# H19R1_Frontend_2.net
KiCad netlist of a schematic drawn in Altium Designer
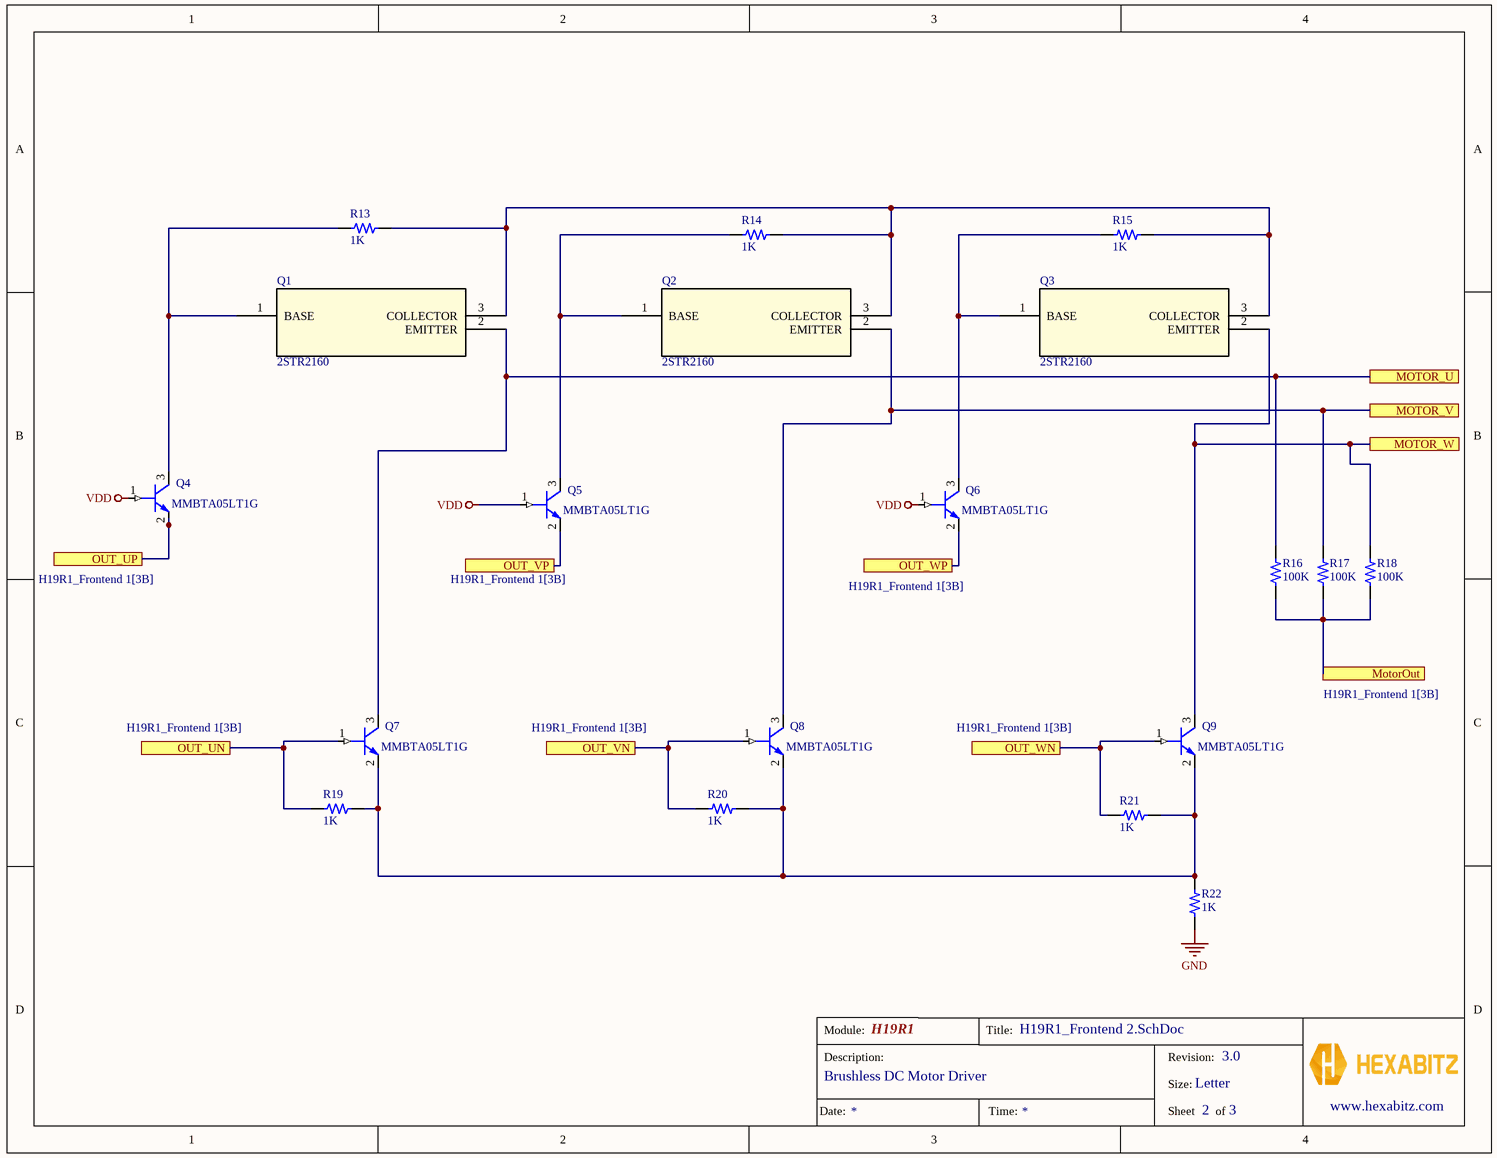
[diagram p0: H19R1_Frontend 2.SchDoc]

(export (version "E")
  (design (tool "Eeschema 10.0.6"))
  (components
    (comp (ref "Q1")
      (value "2STR2160")
      (footprint "SOT23_3P04X1P75X1P9_STM")
      (description "Low voltage fast-switching PNP power transistor")
      (fields (field (name "COPYRIGHT") "Copyright (C) 2025 Ultra Librarian. All rights reserved."))
      (libsource (lib "2STR2160") (part "2STR2160"))
    )
    (comp (ref "Q2")
      (value "2STR2160")
      (footprint "SOT23_3P04X1P75X1P9_STM")
      (description "Low voltage fast-switching PNP power transistor")
      (fields (field (name "COPYRIGHT") "Copyright (C) 2025 Ultra Librarian. All rights reserved."))
      (libsource (lib "2STR2160") (part "2STR2160"))
    )
    (comp (ref "Q3")
      (value "2STR2160")
      (footprint "SOT23_3P04X1P75X1P9_STM")
      (description "Low voltage fast-switching PNP power transistor")
      (fields (field (name "COPYRIGHT") "Copyright (C) 2025 Ultra Librarian. All rights reserved."))
      (libsource (lib "2STR2160") (part "2STR2160"))
    )
    (comp (ref "Q4")
      (value "MMBTA05LT1G")
      (footprint "SOT-23")
      (description "ON Semi MMBTA05LT1G NPN Bipolar Transistor; 0.5 A; 60 V; 3-Pin SOT-23")
      (fields
        (field (name "MANUFACTURER") "ON Semiconductor")
        (field (name "MANUFACTURER PART NUMBER") "MMBTA05LT1G")
      )
      (libsource (lib "Semiconductor") (part "MMBTA05LT1G"))
    )
    (comp (ref "Q5")
      (value "MMBTA05LT1G")
      (footprint "SOT-23")
      (description "ON Semi MMBTA05LT1G NPN Bipolar Transistor; 0.5 A; 60 V; 3-Pin SOT-23")
      (fields
        (field (name "MANUFACTURER") "ON Semiconductor")
        (field (name "MANUFACTURER PART NUMBER") "MMBTA05LT1G")
      )
      (libsource (lib "Semiconductor") (part "MMBTA05LT1G"))
    )
    (comp (ref "Q6")
      (value "MMBTA05LT1G")
      (footprint "SOT-23")
      (description "ON Semi MMBTA05LT1G NPN Bipolar Transistor; 0.5 A; 60 V; 3-Pin SOT-23")
      (fields
        (field (name "MANUFACTURER") "ON Semiconductor")
        (field (name "MANUFACTURER PART NUMBER") "MMBTA05LT1G")
      )
      (libsource (lib "Semiconductor") (part "MMBTA05LT1G"))
    )
    (comp (ref "Q7")
      (value "MMBTA05LT1G")
      (footprint "SOT-23")
      (description "ON Semi MMBTA05LT1G NPN Bipolar Transistor; 0.5 A; 60 V; 3-Pin SOT-23")
      (fields
        (field (name "MANUFACTURER") "ON Semiconductor")
        (field (name "MANUFACTURER PART NUMBER") "MMBTA05LT1G")
      )
      (libsource (lib "Semiconductor") (part "MMBTA05LT1G"))
    )
    (comp (ref "Q8")
      (value "MMBTA05LT1G")
      (footprint "SOT-23")
      (description "ON Semi MMBTA05LT1G NPN Bipolar Transistor; 0.5 A; 60 V; 3-Pin SOT-23")
      (fields
        (field (name "MANUFACTURER") "ON Semiconductor")
        (field (name "MANUFACTURER PART NUMBER") "MMBTA05LT1G")
      )
      (libsource (lib "Semiconductor") (part "MMBTA05LT1G"))
    )
    (comp (ref "Q9")
      (value "MMBTA05LT1G")
      (footprint "SOT-23")
      (description "ON Semi MMBTA05LT1G NPN Bipolar Transistor; 0.5 A; 60 V; 3-Pin SOT-23")
      (fields
        (field (name "MANUFACTURER") "ON Semiconductor")
        (field (name "MANUFACTURER PART NUMBER") "MMBTA05LT1G")
      )
      (libsource (lib "Semiconductor") (part "MMBTA05LT1G"))
    )
    (comp (ref "R13")
      (value "1K")
      (footprint "R0402_3")
      (description "SMD Chip Resistor 1 Kohm ½ 1% 62.5 Mw 0402 [1005 Metric] Thick Film General Purpose")
      (fields
        (field (name "MANUFACTURER") "Yageo")
        (field (name "MANUFACTURER PART NUMBER") "RC0402FR-071KL")
      )
      (libsource (lib "Passive") (part "RC0402FR-071KL"))
    )
    (comp (ref "R14")
      (value "1K")
      (footprint "R0402_3")
      (description "SMD Chip Resistor 1 Kohm ½ 1% 62.5 Mw 0402 [1005 Metric] Thick Film General Purpose")
      (fields
        (field (name "MANUFACTURER") "Yageo")
        (field (name "MANUFACTURER PART NUMBER") "RC0402FR-071KL")
      )
      (libsource (lib "Passive") (part "RC0402FR-071KL"))
    )
    (comp (ref "R15")
      (value "1K")
      (footprint "R0402_3")
      (description "SMD Chip Resistor 1 Kohm ½ 1% 62.5 Mw 0402 [1005 Metric] Thick Film General Purpose")
      (fields
        (field (name "MANUFACTURER") "Yageo")
        (field (name "MANUFACTURER PART NUMBER") "RC0402FR-071KL")
      )
      (libsource (lib "Passive") (part "RC0402FR-071KL"))
    )
    (comp (ref "R16")
      (value "100K")
      (footprint "R0402_3")
      (description "Res Thick Film 0402 100K Ohm 1% 1/10W ±100ppm/°C Molded SMD Punched Carrier T/R")
      (fields
        (field (name "MANUFACTURER") "Panasonic")
        (field (name "MANUFACTURER PART NUMBER") "ERJ-2RKF1003X")
      )
      (libsource (lib "Passive") (part "ERJ-2RKF1003X"))
    )
    (comp (ref "R17")
      (value "100K")
      (footprint "R0402_3")
      (description "Res Thick Film 0402 100K Ohm 1% 1/10W ±100ppm/°C Molded SMD Punched Carrier T/R")
      (fields
        (field (name "MANUFACTURER") "Panasonic")
        (field (name "MANUFACTURER PART NUMBER") "ERJ-2RKF1003X")
      )
      (libsource (lib "Passive") (part "ERJ-2RKF1003X"))
    )
    (comp (ref "R18")
      (value "100K")
      (footprint "R0402_3")
      (description "Res Thick Film 0402 100K Ohm 1% 1/10W ±100ppm/°C Molded SMD Punched Carrier T/R")
      (fields
        (field (name "MANUFACTURER") "Panasonic")
        (field (name "MANUFACTURER PART NUMBER") "ERJ-2RKF1003X")
      )
      (libsource (lib "Passive") (part "ERJ-2RKF1003X"))
    )
    (comp (ref "R19")
      (value "1K")
      (footprint "R0402_3")
      (description "SMD Chip Resistor 1 Kohm ½ 1% 62.5 Mw 0402 [1005 Metric] Thick Film General Purpose")
      (fields
        (field (name "MANUFACTURER") "Yageo")
        (field (name "MANUFACTURER PART NUMBER") "RC0402FR-071KL")
      )
      (libsource (lib "Passive") (part "RC0402FR-071KL"))
    )
    (comp (ref "R20")
      (value "1K")
      (footprint "R0402_3")
      (description "SMD Chip Resistor 1 Kohm ½ 1% 62.5 Mw 0402 [1005 Metric] Thick Film General Purpose")
      (fields
        (field (name "MANUFACTURER") "Yageo")
        (field (name "MANUFACTURER PART NUMBER") "RC0402FR-071KL")
      )
      (libsource (lib "Passive") (part "RC0402FR-071KL"))
    )
    (comp (ref "R21")
      (value "1K")
      (footprint "R0402_3")
      (description "SMD Chip Resistor 1 Kohm ½ 1% 62.5 Mw 0402 [1005 Metric] Thick Film General Purpose")
      (fields
        (field (name "MANUFACTURER") "Yageo")
        (field (name "MANUFACTURER PART NUMBER") "RC0402FR-071KL")
      )
      (libsource (lib "Passive") (part "RC0402FR-071KL"))
    )
    (comp (ref "R22")
      (value "1K")
      (footprint "R0402_3")
      (description "SMD Chip Resistor 1 Kohm ½ 1% 62.5 Mw 0402 [1005 Metric] Thick Film General Purpose")
      (fields
        (field (name "MANUFACTURER") "Yageo")
        (field (name "MANUFACTURER PART NUMBER") "RC0402FR-071KL")
      )
      (libsource (lib "") (part "RC0402FR-071KL_1"))
    )
  )
  (nets
    (net (code "1") (name "/MOTOR_U") (class "Default")
      (node (ref "Q1") (pin "2") (pinfunction "EMITTER_2") (pintype "passive"))
      (node (ref "Q7") (pin "3") (pinfunction "COLLECTOR_3") (pintype "passive"))
      (node (ref "R16") (pin "2") (pinfunction "2_2") (pintype "passive"))
    )
    (net (code "2") (name "/MOTOR_V") (class "Default")
      (node (ref "Q2") (pin "2") (pinfunction "EMITTER_2") (pintype "passive"))
      (node (ref "Q8") (pin "3") (pinfunction "COLLECTOR_3") (pintype "passive"))
      (node (ref "R17") (pin "2") (pinfunction "2_2") (pintype "passive"))
    )
    (net (code "3") (name "/MOTOR_W") (class "Default")
      (node (ref "Q3") (pin "2") (pinfunction "EMITTER_2") (pintype "passive"))
      (node (ref "Q9") (pin "3") (pinfunction "COLLECTOR_3") (pintype "passive"))
      (node (ref "R18") (pin "2") (pinfunction "2_2") (pintype "passive"))
    )
    (net (code "4") (name "/MotorOut") (class "Default")
      (node (ref "R16") (pin "1") (pinfunction "1_1") (pintype "passive"))
      (node (ref "R17") (pin "1") (pinfunction "1_1") (pintype "passive"))
      (node (ref "R18") (pin "1") (pinfunction "1_1") (pintype "passive"))
    )
    (net (code "5") (name "/OUT_UN") (class "Default")
      (node (ref "Q7") (pin "1") (pinfunction "BASE_1") (pintype "input"))
      (node (ref "R19") (pin "1") (pinfunction "1_1") (pintype "passive"))
    )
    (net (code "6") (name "/OUT_UP") (class "Default")
      (node (ref "Q4") (pin "2") (pinfunction "EMITTER_2") (pintype "passive"))
    )
    (net (code "7") (name "/OUT_VN") (class "Default")
      (node (ref "Q8") (pin "1") (pinfunction "BASE_1") (pintype "input"))
      (node (ref "R20") (pin "1") (pinfunction "1_1") (pintype "passive"))
    )
    (net (code "8") (name "/OUT_VP") (class "Default")
      (node (ref "Q5") (pin "2") (pinfunction "EMITTER_2") (pintype "passive"))
    )
    (net (code "9") (name "/OUT_WN") (class "Default")
      (node (ref "Q9") (pin "1") (pinfunction "BASE_1") (pintype "input"))
      (node (ref "R21") (pin "1") (pinfunction "1_1") (pintype "passive"))
    )
    (net (code "10") (name "/OUT_WP") (class "Default")
      (node (ref "Q6") (pin "2") (pinfunction "EMITTER_2") (pintype "passive"))
    )
    (net (code "11") (name "GND") (class "Default")
      (node (ref "R22") (pin "1") (pinfunction "1_1") (pintype "passive"))
    )
    (net (code "12") (name "Net-(Q1-BASE)") (class "Default")
      (node (ref "Q1") (pin "1") (pinfunction "BASE_1") (pintype "passive"))
      (node (ref "Q4") (pin "3") (pinfunction "COLLECTOR_3") (pintype "passive"))
      (node (ref "R13") (pin "1") (pinfunction "1_1") (pintype "passive"))
    )
    (net (code "13") (name "Net-(Q1-COLLECTOR)") (class "Default")
      (node (ref "Q1") (pin "3") (pinfunction "COLLECTOR_3") (pintype "passive"))
      (node (ref "Q2") (pin "3") (pinfunction "COLLECTOR_3") (pintype "passive"))
      (node (ref "Q3") (pin "3") (pinfunction "COLLECTOR_3") (pintype "passive"))
      (node (ref "R13") (pin "2") (pinfunction "2_2") (pintype "passive"))
      (node (ref "R14") (pin "2") (pinfunction "2_2") (pintype "passive"))
      (node (ref "R15") (pin "2") (pinfunction "2_2") (pintype "passive"))
    )
    (net (code "14") (name "Net-(Q2-BASE)") (class "Default")
      (node (ref "Q2") (pin "1") (pinfunction "BASE_1") (pintype "passive"))
      (node (ref "Q5") (pin "3") (pinfunction "COLLECTOR_3") (pintype "passive"))
      (node (ref "R14") (pin "1") (pinfunction "1_1") (pintype "passive"))
    )
    (net (code "15") (name "Net-(Q3-BASE)") (class "Default")
      (node (ref "Q3") (pin "1") (pinfunction "BASE_1") (pintype "passive"))
      (node (ref "Q6") (pin "3") (pinfunction "COLLECTOR_3") (pintype "passive"))
      (node (ref "R15") (pin "1") (pinfunction "1_1") (pintype "passive"))
    )
    (net (code "16") (name "Net-(Q7-EMITTER)") (class "Default")
      (node (ref "Q7") (pin "2") (pinfunction "EMITTER_2") (pintype "passive"))
      (node (ref "Q8") (pin "2") (pinfunction "EMITTER_2") (pintype "passive"))
      (node (ref "Q9") (pin "2") (pinfunction "EMITTER_2") (pintype "passive"))
      (node (ref "R19") (pin "2") (pinfunction "2_2") (pintype "passive"))
      (node (ref "R20") (pin "2") (pinfunction "2_2") (pintype "passive"))
      (node (ref "R21") (pin "2") (pinfunction "2_2") (pintype "passive"))
      (node (ref "R22") (pin "2") (pinfunction "2_2") (pintype "passive"))
    )
    (net (code "17") (name "VDD") (class "Default")
      (node (ref "Q4") (pin "1") (pinfunction "BASE_1") (pintype "input"))
      (node (ref "Q5") (pin "1") (pinfunction "BASE_1") (pintype "input"))
      (node (ref "Q6") (pin "1") (pinfunction "BASE_1") (pintype "input"))
    )
  )
)
